# HydraBus_1_0_Rev1_2plus.net
KiCad netlist of a schematic drawn in EAGLE
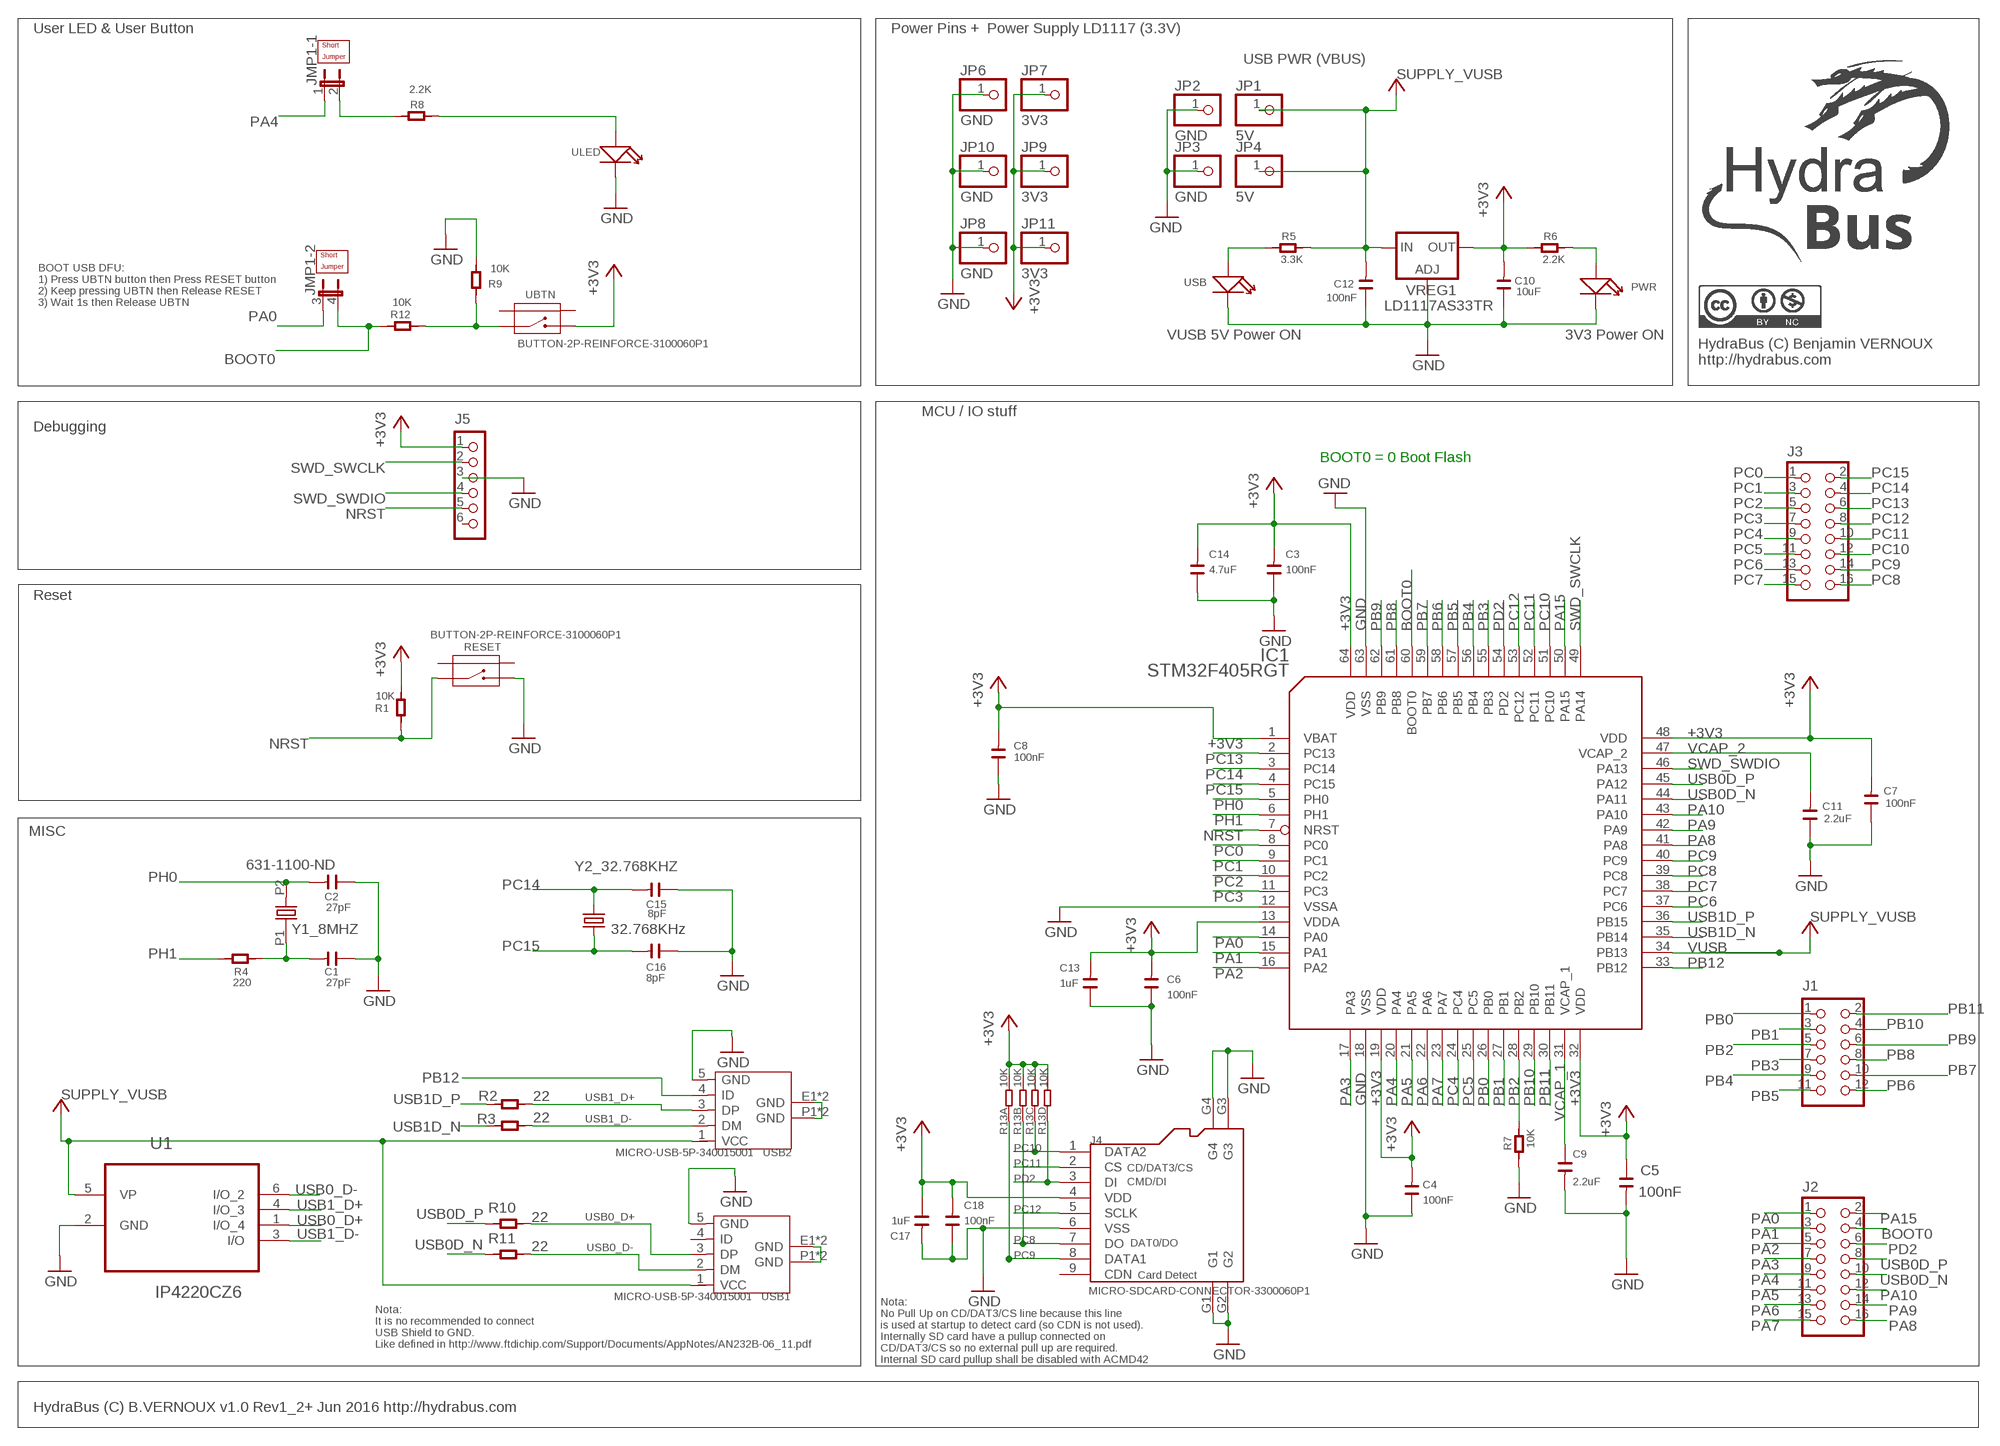
[diagram p0: schematic, sheet 1]

(export (version "E")
  (design (tool "Eeschema 10.0.6"))
  (components
    (comp (ref "C1")
      (value "27pF")
      (footprint "eagle-import:C0603")
      (libsource (lib "eagle-import") (part "C-0603"))
    )
    (comp (ref "C2")
      (value "27pF")
      (footprint "eagle-import:C0603")
      (libsource (lib "eagle-import") (part "C-0603"))
    )
    (comp (ref "C3")
      (value "100nF")
      (footprint "eagle-import:C0603")
      (libsource (lib "eagle-import") (part "C-0603"))
    )
    (comp (ref "C4")
      (value "100nF")
      (footprint "eagle-import:C0603")
      (libsource (lib "eagle-import") (part "C-0603"))
    )
    (comp (ref "C5")
      (value "100nF")
      (footprint "eagle-import:C0603")
      (libsource (lib "eagle-import") (part "C-0603"))
    )
    (comp (ref "C6")
      (value "100nF")
      (footprint "eagle-import:C0603")
      (libsource (lib "eagle-import") (part "C-0603"))
    )
    (comp (ref "C7")
      (value "100nF")
      (footprint "eagle-import:C0603")
      (libsource (lib "eagle-import") (part "C-0603"))
    )
    (comp (ref "C8")
      (value "100nF")
      (footprint "eagle-import:C0603")
      (libsource (lib "eagle-import") (part "C-0603"))
    )
    (comp (ref "C9")
      (value "2.2uF")
      (footprint "eagle-import:C0603")
      (libsource (lib "eagle-import") (part "C-0603"))
    )
    (comp (ref "C10")
      (value "10uF")
      (footprint "eagle-import:C0805")
      (libsource (lib "eagle-import") (part "C-0805"))
    )
    (comp (ref "C11")
      (value "2.2uF")
      (footprint "eagle-import:C0603")
      (libsource (lib "eagle-import") (part "C-0603"))
    )
    (comp (ref "C12")
      (value "100nF")
      (footprint "eagle-import:C0603")
      (libsource (lib "eagle-import") (part "C-0603"))
    )
    (comp (ref "C13")
      (value "1uF")
      (footprint "eagle-import:C0603")
      (libsource (lib "eagle-import") (part "C-0603"))
    )
    (comp (ref "C14")
      (value "4.7uF")
      (footprint "eagle-import:C0603")
      (libsource (lib "eagle-import") (part "C-0603"))
    )
    (comp (ref "C15")
      (value "8pF")
      (footprint "eagle-import:C0603")
      (libsource (lib "eagle-import") (part "C-0603"))
    )
    (comp (ref "C16")
      (value "8pF")
      (footprint "eagle-import:C0603")
      (libsource (lib "eagle-import") (part "C-0603"))
    )
    (comp (ref "C17")
      (value "1uF")
      (footprint "eagle-import:C0603")
      (libsource (lib "eagle-import") (part "C-0603"))
    )
    (comp (ref "C18")
      (value "100nF")
      (footprint "eagle-import:C0603")
      (libsource (lib "eagle-import") (part "C-0603"))
    )
    (comp (ref "IC1")
      (value "STM32F405RGT")
      (footprint "eagle-import:LQFP64")
      (libsource (lib "eagle-import") (part "STM32F405RTG"))
    )
    (comp (ref "J1")
      (value "CON_HEADER_2X06")
      (footprint "eagle-import:M2X6")
      (libsource (lib "eagle-import") (part "CON_HEADER_2X06"))
    )
    (comp (ref "J2")
      (value "CON_HEADER_2X08")
      (footprint "eagle-import:M2X8")
      (libsource (lib "eagle-import") (part "CON_HEADER_2X08"))
    )
    (comp (ref "J3")
      (value "CON_HEADER_2X08")
      (footprint "eagle-import:M2X8")
      (libsource (lib "eagle-import") (part "CON_HEADER_2X08"))
    )
    (comp (ref "J4")
      (value "MICRO-SDCARD-CONNECTOR-3300060P1")
      (footprint "eagle-import:9P-SMD-W-RING")
      (libsource (lib "eagle-import") (part "MICRO-SDCARD-CONNECTOR-3300060P1"))
    )
    (comp (ref "J5")
      (value "CON_HEADER_1X06-PTH")
      (footprint "eagle-import:M1X6")
      (libsource (lib "eagle-import") (part "CON_HEADER_1X06-PTH"))
    )
    (comp (ref "JMP1")
      (value "JP2QE")
      (footprint "eagle-import:JP2Q")
      (libsource (lib "eagle-import") (part "JP2QE"))
    )
    (comp (ref "JMP_UBTN")
      (value "SHORT-JUMPER-2P-3460440P1")
      (footprint "eagle-import:2P-2.54")
      (libsource (lib "eagle-import") (part "SHORT-JUMPER-2P-3460440P1"))
    )
    (comp (ref "JMP_ULED")
      (value "SHORT-JUMPER-2P-3460440P1")
      (footprint "eagle-import:2P-2.54")
      (libsource (lib "eagle-import") (part "SHORT-JUMPER-2P-3460440P1"))
    )
    (comp (ref "JP1")
      (value "5V")
      (footprint "eagle-import:1X01")
      (libsource (lib "eagle-import") (part "PINHD-1X1"))
    )
    (comp (ref "JP2")
      (value "GND")
      (footprint "eagle-import:1X01")
      (libsource (lib "eagle-import") (part "PINHD-1X1"))
    )
    (comp (ref "JP3")
      (value "GND")
      (footprint "eagle-import:1X01")
      (libsource (lib "eagle-import") (part "PINHD-1X1"))
    )
    (comp (ref "JP4")
      (value "5V")
      (footprint "eagle-import:1X01")
      (libsource (lib "eagle-import") (part "PINHD-1X1"))
    )
    (comp (ref "JP6")
      (value "GND")
      (footprint "eagle-import:1X01")
      (libsource (lib "eagle-import") (part "PINHD-1X1"))
    )
    (comp (ref "JP7")
      (value "3V3")
      (footprint "eagle-import:1X01")
      (libsource (lib "eagle-import") (part "PINHD-1X1"))
    )
    (comp (ref "JP8")
      (value "GND")
      (footprint "eagle-import:1X01")
      (libsource (lib "eagle-import") (part "PINHD-1X1"))
    )
    (comp (ref "JP9")
      (value "3V3")
      (footprint "eagle-import:1X01")
      (libsource (lib "eagle-import") (part "PINHD-1X1"))
    )
    (comp (ref "JP10")
      (value "GND")
      (footprint "eagle-import:1X01")
      (libsource (lib "eagle-import") (part "PINHD-1X1"))
    )
    (comp (ref "JP11")
      (value "3V3")
      (footprint "eagle-import:1X01")
      (libsource (lib "eagle-import") (part "PINHD-1X1"))
    )
    (comp (ref "PWR")
      (value "LED")
      (footprint "eagle-import:LED0603")
      (libsource (lib "eagle-import") (part "LED"))
    )
    (comp (ref "R1")
      (value "10K")
      (footprint "eagle-import:R0603")
      (libsource (lib "eagle-import") (part "R-0603"))
    )
    (comp (ref "R2")
      (value "22")
      (footprint "eagle-import:R0603")
      (libsource (lib "eagle-import") (part "R-0603"))
    )
    (comp (ref "R3")
      (value "22")
      (footprint "eagle-import:R0603")
      (libsource (lib "eagle-import") (part "R-0603"))
    )
    (comp (ref "R4")
      (value "220")
      (footprint "eagle-import:R0603")
      (libsource (lib "eagle-import") (part "R-0603"))
    )
    (comp (ref "R5")
      (value "3.3K")
      (footprint "eagle-import:R0603")
      (libsource (lib "eagle-import") (part "R-0603"))
    )
    (comp (ref "R6")
      (value "2.2K")
      (footprint "eagle-import:R0603")
      (libsource (lib "eagle-import") (part "R-0603"))
    )
    (comp (ref "R7")
      (value "10K")
      (footprint "eagle-import:R0603")
      (libsource (lib "eagle-import") (part "R-0603"))
    )
    (comp (ref "R8")
      (value "2.2K")
      (footprint "eagle-import:R0603")
      (libsource (lib "eagle-import") (part "R-0603"))
    )
    (comp (ref "R9")
      (value "10K")
      (footprint "eagle-import:R0603")
      (libsource (lib "eagle-import") (part "R-0603"))
    )
    (comp (ref "R10")
      (value "22")
      (footprint "eagle-import:R0603")
      (libsource (lib "eagle-import") (part "R-0603"))
    )
    (comp (ref "R11")
      (value "22")
      (footprint "eagle-import:R0603")
      (libsource (lib "eagle-import") (part "R-0603"))
    )
    (comp (ref "R12")
      (value "10K")
      (footprint "eagle-import:R0603")
      (libsource (lib "eagle-import") (part "R-0603"))
    )
    (comp (ref "R13")
      (value "10K")
      (footprint "eagle-import:R1206-8")
      (fields (field (name "OPL") "0040070P1 SMD RES ARRAY 10K OHM 4 RES 1206"))
      (libsource (lib "eagle-import") (part "R-4R"))
    )
    (comp (ref "RESET")
      (value "BUTTON-2P-REINFORCE-3100060P1")
      (footprint "eagle-import:4P-SMD-7.0X3.5X3.5H-90D")
      (libsource (lib "eagle-import") (part "BUTTON-2P-REINFORCE-3100060P1"))
    )
    (comp (ref "U1")
      (value "IP4220CZ6")
      (footprint "eagle-import:SOT95P275X110-6N")
      (libsource (lib "eagle-import") (part "IP4220CZ6"))
    )
    (comp (ref "UBTN")
      (value "BUTTON-2P-REINFORCE-3100060P1")
      (footprint "eagle-import:4P-SMD-7.0X3.5X3.5H-90D")
      (libsource (lib "eagle-import") (part "BUTTON-2P-REINFORCE-3100060P1"))
    )
    (comp (ref "ULED")
      (value "LED")
      (footprint "eagle-import:LED0603")
      (libsource (lib "eagle-import") (part "LED"))
    )
    (comp (ref "USB")
      (value "LED")
      (footprint "eagle-import:LED0603")
      (libsource (lib "eagle-import") (part "LED"))
    )
    (comp (ref "USB1")
      (value "MICRO-USB-5P-340015001")
      (footprint "eagle-import:B-SMD-5P")
      (libsource (lib "eagle-import") (part "MICRO-USB-5P-340015001"))
    )
    (comp (ref "USB2")
      (value "MICRO-USB-5P-340015001")
      (footprint "eagle-import:B-SMD-5P")
      (libsource (lib "eagle-import") (part "MICRO-USB-5P-340015001"))
    )
    (comp (ref "VREG1")
      (value "LD1117AS33TR")
      (footprint "eagle-import:SOT223")
      (libsource (lib "eagle-import") (part "LD117A?S33TR"))
    )
    (comp (ref "Y1_8MHZ")
      (value "631-1100-ND")
      (footprint "eagle-import:HC-49U-PTH")
      (libsource (lib "eagle-import") (part "OSC-XTAL-HC-49U-PTH"))
    )
    (comp (ref "Y2_32.768KHZ")
      (value "32.768KHz")
      (footprint "eagle-import:TC38H")
      (libsource (lib "eagle-import") (part "CRYSTALTC38H"))
    )
  )
  (nets
    (net (code "1") (name "+3V3") (class "Default")
      (node (ref "C10") (pin "1") (pinfunction "1_1") (pintype "bidirectional"))
      (node (ref "C13") (pin "1") (pinfunction "1_1") (pintype "bidirectional"))
      (node (ref "C14") (pin "1") (pinfunction "1_1") (pintype "bidirectional"))
      (node (ref "C17") (pin "2") (pinfunction "2_2") (pintype "bidirectional"))
      (node (ref "C18") (pin "1") (pinfunction "1_1") (pintype "bidirectional"))
      (node (ref "C3") (pin "1") (pinfunction "1_1") (pintype "bidirectional"))
      (node (ref "C4") (pin "1") (pinfunction "1_1") (pintype "bidirectional"))
      (node (ref "C5") (pin "2") (pinfunction "2_2") (pintype "bidirectional"))
      (node (ref "C6") (pin "1") (pinfunction "1_1") (pintype "bidirectional"))
      (node (ref "C7") (pin "1") (pinfunction "1_1") (pintype "bidirectional"))
      (node (ref "C8") (pin "1") (pinfunction "1_1") (pintype "bidirectional"))
      (node (ref "IC1") (pin "1") (pinfunction "VBAT_1") (pintype "power_in"))
      (node (ref "IC1") (pin "13") (pinfunction "VDDA_13") (pintype "power_in"))
      (node (ref "IC1") (pin "19") (pinfunction "VDD_19") (pintype "power_in"))
      (node (ref "IC1") (pin "32") (pinfunction "VDD_32") (pintype "power_in"))
      (node (ref "IC1") (pin "48") (pinfunction "VDD_48") (pintype "power_in"))
      (node (ref "IC1") (pin "64") (pinfunction "VDD_64") (pintype "power_in"))
      (node (ref "J4") (pin "4") (pinfunction "VDD_4") (pintype "bidirectional"))
      (node (ref "J5") (pin "1") (pinfunction "1_1") (pintype "bidirectional"))
      (node (ref "JP11") (pin "1") (pinfunction "1_1") (pintype "passive"))
      (node (ref "JP7") (pin "1") (pinfunction "1_1") (pintype "passive"))
      (node (ref "JP9") (pin "1") (pinfunction "1_1") (pintype "passive"))
      (node (ref "R1") (pin "2") (pinfunction "2_2") (pintype "bidirectional"))
      (node (ref "R13") (pin "5") (pinfunction "2_5") (pintype "passive"))
      (node (ref "R13") (pin "6") (pinfunction "2_6") (pintype "passive"))
      (node (ref "R13") (pin "7") (pinfunction "2_7") (pintype "passive"))
      (node (ref "R13") (pin "8") (pinfunction "2_8") (pintype "passive"))
      (node (ref "R6") (pin "2") (pinfunction "2_2") (pintype "bidirectional"))
      (node (ref "UBTN") (pin "2") (pinfunction "2_2") (pintype "bidirectional"))
      (node (ref "VREG1") (pin "4") (pinfunction "OUT_4") (pintype "passive"))
    )
    (net (code "2") (name "/BOOT0") (class "Default")
      (node (ref "IC1") (pin "60") (pinfunction "BOOT0_60") (pintype "bidirectional"))
      (node (ref "J2") (pin "4") (pinfunction "4_4") (pintype "passive"))
      (node (ref "JMP1") (pin "4") (pinfunction "2_4") (pintype "passive"))
      (node (ref "R12") (pin "2") (pinfunction "2_2") (pintype "bidirectional"))
    )
    (net (code "3") (name "/NRST") (class "Default")
      (node (ref "IC1") (pin "7") (pinfunction "NRST_7") (pintype "input"))
      (node (ref "J5") (pin "5") (pinfunction "5_5") (pintype "passive"))
      (node (ref "R1") (pin "1") (pinfunction "1_1") (pintype "bidirectional"))
      (node (ref "RESET") (pin "1") (pinfunction "1_1") (pintype "bidirectional"))
    )
    (net (code "4") (name "/PA0") (class "Default")
      (node (ref "IC1") (pin "14") (pinfunction "PA0_14") (pintype "bidirectional"))
      (node (ref "J2") (pin "1") (pinfunction "1_1") (pintype "passive"))
      (node (ref "JMP1") (pin "3") (pinfunction "1_3") (pintype "passive"))
    )
    (net (code "5") (name "/PA1") (class "Default")
      (node (ref "IC1") (pin "15") (pinfunction "PA1_15") (pintype "bidirectional"))
      (node (ref "J2") (pin "3") (pinfunction "3_3") (pintype "passive"))
    )
    (net (code "6") (name "/PA2") (class "Default")
      (node (ref "IC1") (pin "16") (pinfunction "PA2_16") (pintype "bidirectional"))
      (node (ref "J2") (pin "5") (pinfunction "5_5") (pintype "passive"))
    )
    (net (code "7") (name "/PA3") (class "Default")
      (node (ref "IC1") (pin "17") (pinfunction "PA3_17") (pintype "bidirectional"))
      (node (ref "J2") (pin "7") (pinfunction "7_7") (pintype "passive"))
    )
    (net (code "8") (name "/PA4") (class "Default")
      (node (ref "IC1") (pin "20") (pinfunction "PA4_20") (pintype "bidirectional"))
      (node (ref "J2") (pin "9") (pinfunction "9_9") (pintype "passive"))
      (node (ref "JMP1") (pin "1") (pinfunction "1_1") (pintype "passive"))
    )
    (net (code "9") (name "/PA5") (class "Default")
      (node (ref "IC1") (pin "21") (pinfunction "PA5_21") (pintype "bidirectional"))
      (node (ref "J2") (pin "11") (pinfunction "11_11") (pintype "passive"))
    )
    (net (code "10") (name "/PA6") (class "Default")
      (node (ref "IC1") (pin "22") (pinfunction "PA6_22") (pintype "bidirectional"))
      (node (ref "J2") (pin "13") (pinfunction "13_13") (pintype "passive"))
    )
    (net (code "11") (name "/PA7") (class "Default")
      (node (ref "IC1") (pin "23") (pinfunction "PA7_23") (pintype "bidirectional"))
      (node (ref "J2") (pin "15") (pinfunction "15_15") (pintype "passive"))
    )
    (net (code "12") (name "/PA8") (class "Default")
      (node (ref "IC1") (pin "41") (pinfunction "PA8_41") (pintype "bidirectional"))
      (node (ref "J2") (pin "16") (pinfunction "16_16") (pintype "passive"))
    )
    (net (code "13") (name "/PA9") (class "Default")
      (node (ref "IC1") (pin "42") (pinfunction "PA9_42") (pintype "bidirectional"))
      (node (ref "J2") (pin "14") (pinfunction "14_14") (pintype "passive"))
    )
    (net (code "14") (name "/PA10") (class "Default")
      (node (ref "IC1") (pin "43") (pinfunction "PA10_43") (pintype "bidirectional"))
      (node (ref "J2") (pin "12") (pinfunction "12_12") (pintype "passive"))
    )
    (net (code "15") (name "/PA15") (class "Default")
      (node (ref "IC1") (pin "50") (pinfunction "PA15_50") (pintype "bidirectional"))
      (node (ref "J2") (pin "2") (pinfunction "2_2") (pintype "passive"))
    )
    (net (code "16") (name "/PB0") (class "Default")
      (node (ref "IC1") (pin "26") (pinfunction "PB0_26") (pintype "bidirectional"))
      (node (ref "J1") (pin "1") (pinfunction "1_1") (pintype "passive"))
    )
    (net (code "17") (name "/PB1") (class "Default")
      (node (ref "IC1") (pin "27") (pinfunction "PB1_27") (pintype "bidirectional"))
      (node (ref "J1") (pin "3") (pinfunction "3_3") (pintype "passive"))
    )
    (net (code "18") (name "/PB2") (class "Default")
      (node (ref "IC1") (pin "28") (pinfunction "PB2_28") (pintype "bidirectional"))
      (node (ref "J1") (pin "5") (pinfunction "5_5") (pintype "passive"))
      (node (ref "R7") (pin "1") (pinfunction "1_1") (pintype "bidirectional"))
    )
    (net (code "19") (name "/PB3") (class "Default")
      (node (ref "IC1") (pin "55") (pinfunction "PB3_55") (pintype "bidirectional"))
      (node (ref "J1") (pin "7") (pinfunction "7_7") (pintype "passive"))
    )
    (net (code "20") (name "/PB4") (class "Default")
      (node (ref "IC1") (pin "56") (pinfunction "PB4_56") (pintype "bidirectional"))
      (node (ref "J1") (pin "9") (pinfunction "9_9") (pintype "passive"))
    )
    (net (code "21") (name "/PB5") (class "Default")
      (node (ref "IC1") (pin "57") (pinfunction "PB5_57") (pintype "bidirectional"))
      (node (ref "J1") (pin "11") (pinfunction "11_11") (pintype "passive"))
    )
    (net (code "22") (name "/PB6") (class "Default")
      (node (ref "IC1") (pin "58") (pinfunction "PB6_58") (pintype "bidirectional"))
      (node (ref "J1") (pin "12") (pinfunction "12_12") (pintype "passive"))
    )
    (net (code "23") (name "/PB7") (class "Default")
      (node (ref "IC1") (pin "59") (pinfunction "PB7_59") (pintype "bidirectional"))
      (node (ref "J1") (pin "10") (pinfunction "10_10") (pintype "passive"))
    )
    (net (code "24") (name "/PB8") (class "Default")
      (node (ref "IC1") (pin "61") (pinfunction "PB8_61") (pintype "bidirectional"))
      (node (ref "J1") (pin "8") (pinfunction "8_8") (pintype "passive"))
    )
    (net (code "25") (name "/PB9") (class "Default")
      (node (ref "IC1") (pin "62") (pinfunction "PB9_62") (pintype "bidirectional"))
      (node (ref "J1") (pin "6") (pinfunction "6_6") (pintype "passive"))
    )
    (net (code "26") (name "/PB10") (class "Default")
      (node (ref "IC1") (pin "29") (pinfunction "PB10_29") (pintype "bidirectional"))
      (node (ref "J1") (pin "4") (pinfunction "4_4") (pintype "passive"))
    )
    (net (code "27") (name "/PB11") (class "Default")
      (node (ref "IC1") (pin "30") (pinfunction "PB11_30") (pintype "bidirectional"))
      (node (ref "J1") (pin "2") (pinfunction "2_2") (pintype "passive"))
    )
    (net (code "28") (name "/PB12") (class "Default")
      (node (ref "IC1") (pin "33") (pinfunction "PB12_33") (pintype "bidirectional"))
      (node (ref "USB2") (pin "4") (pinfunction "ID_4") (pintype "bidirectional"))
    )
    (net (code "29") (name "/PC0") (class "Default")
      (node (ref "IC1") (pin "8") (pinfunction "PC0_8") (pintype "bidirectional"))
      (node (ref "J3") (pin "1") (pinfunction "1_1") (pintype "passive"))
    )
    (net (code "30") (name "/PC1") (class "Default")
      (node (ref "IC1") (pin "9") (pinfunction "PC1_9") (pintype "bidirectional"))
      (node (ref "J3") (pin "3") (pinfunction "3_3") (pintype "passive"))
    )
    (net (code "31") (name "/PC2") (class "Default")
      (node (ref "IC1") (pin "10") (pinfunction "PC2_10") (pintype "bidirectional"))
      (node (ref "J3") (pin "5") (pinfunction "5_5") (pintype "passive"))
    )
    (net (code "32") (name "/PC3") (class "Default")
      (node (ref "IC1") (pin "11") (pinfunction "PC3_11") (pintype "bidirectional"))
      (node (ref "J3") (pin "7") (pinfunction "7_7") (pintype "passive"))
    )
    (net (code "33") (name "/PC4") (class "Default")
      (node (ref "IC1") (pin "24") (pinfunction "PC4_24") (pintype "bidirectional"))
      (node (ref "J3") (pin "9") (pinfunction "9_9") (pintype "passive"))
    )
    (net (code "34") (name "/PC5") (class "Default")
      (node (ref "IC1") (pin "25") (pinfunction "PC5_25") (pintype "bidirectional"))
      (node (ref "J3") (pin "11") (pinfunction "11_11") (pintype "passive"))
    )
    (net (code "35") (name "/PC6") (class "Default")
      (node (ref "IC1") (pin "37") (pinfunction "PC6_37") (pintype "bidirectional"))
      (node (ref "J3") (pin "13") (pinfunction "13_13") (pintype "passive"))
    )
    (net (code "36") (name "/PC7") (class "Default")
      (node (ref "IC1") (pin "38") (pinfunction "PC7_38") (pintype "bidirectional"))
      (node (ref "J3") (pin "15") (pinfunction "15_15") (pintype "passive"))
    )
    (net (code "37") (name "/PC8") (class "Default")
      (node (ref "IC1") (pin "39") (pinfunction "PC8_39") (pintype "bidirectional"))
      (node (ref "J3") (pin "16") (pinfunction "16_16") (pintype "passive"))
      (node (ref "J4") (pin "7") (pinfunction "DO_7") (pintype "bidirectional"))
      (node (ref "R13") (pin "2") (pinfunction "1_2") (pintype "passive"))
    )
    (net (code "38") (name "/PC9") (class "Default")
      (node (ref "IC1") (pin "40") (pinfunction "PC9_40") (pintype "bidirectional"))
      (node (ref "J3") (pin "14") (pinfunction "14_14") (pintype "passive"))
      (node (ref "J4") (pin "8") (pinfunction "DATA1_8") (pintype "bidirectional"))
      (node (ref "R13") (pin "1") (pinfunction "1_1") (pintype "passive"))
    )
    (net (code "39") (name "/PC10") (class "Default")
      (node (ref "IC1") (pin "51") (pinfunction "PC10_51") (pintype "bidirectional"))
      (node (ref "J3") (pin "12") (pinfunction "12_12") (pintype "passive"))
      (node (ref "J4") (pin "1") (pinfunction "DATA2_1") (pintype "bidirectional"))
      (node (ref "R13") (pin "3") (pinfunction "1_3") (pintype "passive"))
    )
    (net (code "40") (name "/PC11") (class "Default")
      (node (ref "IC1") (pin "52") (pinfunction "PC11_52") (pintype "bidirectional"))
      (node (ref "J3") (pin "10") (pinfunction "10_10") (pintype "passive"))
      (node (ref "J4") (pin "2") (pinfunction "CS_2") (pintype "bidirectional"))
    )
    (net (code "41") (name "/PC12") (class "Default")
      (node (ref "IC1") (pin "53") (pinfunction "PC12_53") (pintype "bidirectional"))
      (node (ref "J3") (pin "8") (pinfunction "8_8") (pintype "passive"))
      (node (ref "J4") (pin "5") (pinfunction "SCLK_5") (pintype "bidirectional"))
    )
    (net (code "42") (name "/PC13") (class "Default")
      (node (ref "IC1") (pin "2") (pinfunction "PC13_2") (pintype "bidirectional"))
      (node (ref "J3") (pin "6") (pinfunction "6_6") (pintype "passive"))
    )
    (net (code "43") (name "/PC14") (class "Default")
      (node (ref "C15") (pin "1") (pinfunction "1_1") (pintype "bidirectional"))
      (node (ref "IC1") (pin "3") (pinfunction "PC14_3") (pintype "bidirectional"))
      (node (ref "J3") (pin "4") (pinfunction "4_4") (pintype "passive"))
      (node (ref "Y2_32.768KHZ") (pin "2") (pinfunction "2_2") (pintype "passive"))
    )
    (net (code "44") (name "/PC15") (class "Default")
      (node (ref "C16") (pin "1") (pinfunction "1_1") (pintype "bidirectional"))
      (node (ref "IC1") (pin "4") (pinfunction "PC15_4") (pintype "bidirectional"))
      (node (ref "J3") (pin "2") (pinfunction "2_2") (pintype "passive"))
      (node (ref "Y2_32.768KHZ") (pin "1") (pinfunction "1_1") (pintype "passive"))
    )
    (net (code "45") (name "/PD2") (class "Default")
      (node (ref "IC1") (pin "54") (pinfunction "PD2_54") (pintype "bidirectional"))
      (node (ref "J2") (pin "6") (pinfunction "6_6") (pintype "passive"))
      (node (ref "J4") (pin "3") (pinfunction "DI_3") (pintype "bidirectional"))
      (node (ref "R13") (pin "4") (pinfunction "1_4") (pintype "passive"))
    )
    (net (code "46") (name "/PH0") (class "Default")
      (node (ref "C2") (pin "1") (pinfunction "1_1") (pintype "bidirectional"))
      (node (ref "IC1") (pin "5") (pinfunction "PH0_5") (pintype "bidirectional"))
      (node (ref "Y1_8MHZ") (pin "P2") (pinfunction "2_P2") (pintype "passive"))
    )
    (net (code "47") (name "/PH1") (class "Default")
      (node (ref "IC1") (pin "6") (pinfunction "PH1_6") (pintype "bidirectional"))
      (node (ref "R4") (pin "2") (pinfunction "2_2") (pintype "bidirectional"))
    )
    (net (code "48") (name "/SWD_SWCLK") (class "Default")
      (node (ref "IC1") (pin "49") (pinfunction "PA14_49") (pintype "bidirectional"))
      (node (ref "J5") (pin "2") (pinfunction "2_2") (pintype "bidirectional"))
    )
    (net (code "49") (name "/SWD_SWDIO") (class "Default")
      (node (ref "IC1") (pin "46") (pinfunction "PA13_46") (pintype "bidirectional"))
      (node (ref "J5") (pin "4") (pinfunction "4_4") (pintype "passive"))
    )
    (net (code "50") (name "/USB0D_N") (class "Default")
      (node (ref "IC1") (pin "44") (pinfunction "PA11_44") (pintype "bidirectional"))
      (node (ref "J2") (pin "10") (pinfunction "10_10") (pintype "passive"))
      (node (ref "R11") (pin "2") (pinfunction "2_2") (pintype "bidirectional"))
    )
    (net (code "51") (name "/USB0D_P") (class "Default")
      (node (ref "IC1") (pin "45") (pinfunction "PA12_45") (pintype "bidirectional"))
      (node (ref "J2") (pin "8") (pinfunction "8_8") (pintype "passive"))
      (node (ref "R10") (pin "2") (pinfunction "2_2") (pintype "bidirectional"))
    )
    (net (code "52") (name "/USB0_D+") (class "Default")
      (node (ref "R10") (pin "1") (pinfunction "1_1") (pintype "bidirectional"))
      (node (ref "U1") (pin "1") (pinfunction "I/O_4_1") (pintype "bidirectional"))
      (node (ref "USB1") (pin "3") (pinfunction "DP_3") (pintype "bidirectional"))
    )
    (net (code "53") (name "/USB0_D-") (class "Default")
      (node (ref "R11") (pin "1") (pinfunction "1_1") (pintype "bidirectional"))
      (node (ref "U1") (pin "6") (pinfunction "I/O_2_6") (pintype "bidirectional"))
      (node (ref "USB1") (pin "2") (pinfunction "DM_2") (pintype "bidirectional"))
    )
    (net (code "54") (name "/USB1D_N") (class "Default")
      (node (ref "IC1") (pin "35") (pinfunction "PB14_35") (pintype "bidirectional"))
      (node (ref "R3") (pin "2") (pinfunction "2_2") (pintype "bidirectional"))
    )
    (net (code "55") (name "/USB1D_P") (class "Default")
      (node (ref "IC1") (pin "36") (pinfunction "PB15_36") (pintype "bidirectional"))
      (node (ref "R2") (pin "2") (pinfunction "2_2") (pintype "bidirectional"))
    )
    (net (code "56") (name "/USB1_D+") (class "Default")
      (node (ref "R2") (pin "1") (pinfunction "1_1") (pintype "bidirectional"))
      (node (ref "U1") (pin "4") (pinfunction "I/O_3_4") (pintype "bidirectional"))
      (node (ref "USB2") (pin "3") (pinfunction "DP_3") (pintype "bidirectional"))
    )
    (net (code "57") (name "/USB1_D-") (class "Default")
      (node (ref "R3") (pin "1") (pinfunction "1_1") (pintype "bidirectional"))
      (node (ref "U1") (pin "3") (pinfunction "I/O_3") (pintype "bidirectional"))
      (node (ref "USB2") (pin "2") (pinfunction "DM_2") (pintype "bidirectional"))
    )
    (net (code "58") (name "/VCAP_1") (class "Default")
      (node (ref "C9") (pin "2") (pinfunction "2_2") (pintype "bidirectional"))
      (node (ref "IC1") (pin "31") (pinfunction "VCAP_1_31") (pintype "passive"))
    )
    (net (code "59") (name "/VCAP_2") (class "Default")
      (node (ref "C11") (pin "1") (pinfunction "1_1") (pintype "bidirectional"))
      (node (ref "IC1") (pin "47") (pinfunction "VCAP_2_47") (pintype "passive"))
    )
    (net (code "60") (name "GND") (class "Default")
      (node (ref "C1") (pin "2") (pinfunction "2_2") (pintype "bidirectional"))
      (node (ref "C10") (pin "2") (pinfunction "2_2") (pintype "bidirectional"))
      (node (ref "C11") (pin "2") (pinfunction "2_2") (pintype "bidirectional"))
      (node (ref "C12") (pin "2") (pinfunction "2_2") (pintype "bidirectional"))
      (node (ref "C13") (pin "2") (pinfunction "2_2") (pintype "bidirectional"))
      (node (ref "C14") (pin "2") (pinfunction "2_2") (pintype "bidirectional"))
      (node (ref "C15") (pin "2") (pinfunction "2_2") (pintype "bidirectional"))
      (node (ref "C16") (pin "2") (pinfunction "2_2") (pintype "bidirectional"))
      (node (ref "C17") (pin "1") (pinfunction "1_1") (pintype "bidirectional"))
      (node (ref "C18") (pin "2") (pinfunction "2_2") (pintype "bidirectional"))
      (node (ref "C2") (pin "2") (pinfunction "2_2") (pintype "bidirectional"))
      (node (ref "C3") (pin "2") (pinfunction "2_2") (pintype "bidirectional"))
      (node (ref "C4") (pin "2") (pinfunction "2_2") (pintype "bidirectional"))
      (node (ref "C5") (pin "1") (pinfunction "1_1") (pintype "bidirectional"))
      (node (ref "C6") (pin "2") (pinfunction "2_2") (pintype "bidirectional"))
      (node (ref "C7") (pin "2") (pinfunction "2_2") (pintype "bidirectional"))
      (node (ref "C8") (pin "2") (pinfunction "2_2") (pintype "bidirectional"))
      (node (ref "C9") (pin "1") (pinfunction "1_1") (pintype "bidirectional"))
      (node (ref "IC1") (pin "12") (pinfunction "VSSA_12") (pintype "power_in"))
      (node (ref "IC1") (pin "18") (pinfunction "VSS_18") (pintype "power_in"))
      (node (ref "IC1") (pin "63") (pinfunction "VSS_63") (pintype "power_in"))
      (node (ref "J4") (pin "6") (pinfunction "VSS_6") (pintype "bidirectional"))
      (node (ref "J4") (pin "G1") (pinfunction "G1_G1") (pintype "bidirectional"))
      (node (ref "J4") (pin "G2") (pinfunction "G2_G2") (pintype "bidirectional"))
      (node (ref "J4") (pin "G3") (pinfunction "G3_G3") (pintype "bidirectional"))
      (node (ref "J4") (pin "G4") (pinfunction "G4_G4") (pintype "bidirectional"))
      (node (ref "J5") (pin "3") (pinfunction "3_3") (pintype "passive"))
      (node (ref "JP10") (pin "1") (pinfunction "1_1") (pintype "passive"))
      (node (ref "JP2") (pin "1") (pinfunction "1_1") (pintype "passive"))
      (node (ref "JP3") (pin "1") (pinfunction "1_1") (pintype "passive"))
      (node (ref "JP6") (pin "1") (pinfunction "1_1") (pintype "passive"))
      (node (ref "JP8") (pin "1") (pinfunction "1_1") (pintype "passive"))
      (node (ref "PWR") (pin "-") (pinfunction "-_-") (pintype "passive"))
      (node (ref "R7") (pin "2") (pinfunction "2_2") (pintype "bidirectional"))
      (node (ref "R9") (pin "2") (pinfunction "2_2") (pintype "bidirectional"))
      (node (ref "RESET") (pin "2") (pinfunction "2_2") (pintype "bidirectional"))
      (node (ref "U1") (pin "2") (pinfunction "GND_2") (pintype "passive"))
      (node (ref "ULED") (pin "-") (pinfunction "-_-") (pintype "passive"))
      (node (ref "USB") (pin "-") (pinfunction "-_-") (pintype "passive"))
      (node (ref "USB1") (pin "5") (pinfunction "GND_5") (pintype "bidirectional"))
      (node (ref "USB2") (pin "5") (pinfunction "GND_5") (pintype "bidirectional"))
      (node (ref "VREG1") (pin "1") (pinfunction "ADJ_1") (pintype "input"))
    )
    (net (code "61") (name "Net-(JMP1-Pad2)") (class "Default")
      (node (ref "JMP1") (pin "2") (pinfunction "2_2") (pintype "passive"))
      (node (ref "R8") (pin "2") (pinfunction "2_2") (pintype "bidirectional"))
    )
    (net (code "62") (name "Net-(PWR-Pad+)") (class "Default")
      (node (ref "PWR") (pin "+") (pinfunction "+_+") (pintype "passive"))
      (node (ref "R6") (pin "1") (pinfunction "1_1") (pintype "bidirectional"))
    )
    (net (code "63") (name "Net-(R5-Pad2)") (class "Default")
      (node (ref "R5") (pin "2") (pinfunction "2_2") (pintype "bidirectional"))
      (node (ref "USB") (pin "+") (pinfunction "+_+") (pintype "passive"))
    )
    (net (code "64") (name "Net-(R8-Pad1)") (class "Default")
      (node (ref "R8") (pin "1") (pinfunction "1_1") (pintype "bidirectional"))
      (node (ref "ULED") (pin "+") (pinfunction "+_+") (pintype "passive"))
    )
    (net (code "65") (name "Net-(R12-Pad1)") (class "Default")
      (node (ref "R12") (pin "1") (pinfunction "1_1") (pintype "bidirectional"))
      (node (ref "R9") (pin "1") (pinfunction "1_1") (pintype "bidirectional"))
      (node (ref "UBTN") (pin "1") (pinfunction "1_1") (pintype "bidirectional"))
    )
    (net (code "66") (name "Net-(USB1-GND-PadE1)") (class "Default")
      (node (ref "USB1") (pin "E1") (pinfunction "GND_E1") (pintype "bidirectional"))
      (node (ref "USB1") (pin "E2") (pinfunction "GND_E2") (pintype "bidirectional"))
      (node (ref "USB1") (pin "P1") (pinfunction "GND_P1") (pintype "bidirectional"))
      (node (ref "USB1") (pin "P2") (pinfunction "GND_P2") (pintype "bidirectional"))
    )
    (net (code "67") (name "Net-(USB2-GND-PadE1)") (class "Default")
      (node (ref "USB2") (pin "E1") (pinfunction "GND_E1") (pintype "bidirectional"))
      (node (ref "USB2") (pin "E2") (pinfunction "GND_E2") (pintype "bidirectional"))
      (node (ref "USB2") (pin "P1") (pinfunction "GND_P1") (pintype "bidirectional"))
      (node (ref "USB2") (pin "P2") (pinfunction "GND_P2") (pintype "bidirectional"))
    )
    (net (code "68") (name "Net-(Y1_8MHZ-1)") (class "Default")
      (node (ref "C1") (pin "1") (pinfunction "1_1") (pintype "bidirectional"))
      (node (ref "R4") (pin "1") (pinfunction "1_1") (pintype "bidirectional"))
      (node (ref "Y1_8MHZ") (pin "P1") (pinfunction "1_P1") (pintype "passive"))
    )
    (net (code "69") (name "SUPPLY_VUSB") (class "Default")
      (node (ref "C12") (pin "1") (pinfunction "1_1") (pintype "bidirectional"))
      (node (ref "IC1") (pin "34") (pinfunction "PB13_34") (pintype "bidirectional"))
      (node (ref "JP1") (pin "1") (pinfunction "1_1") (pintype "passive"))
      (node (ref "JP4") (pin "1") (pinfunction "1_1") (pintype "passive"))
      (node (ref "R5") (pin "1") (pinfunction "1_1") (pintype "bidirectional"))
      (node (ref "U1") (pin "5") (pinfunction "VP_5") (pintype "power_in"))
      (node (ref "USB1") (pin "1") (pinfunction "VCC_1") (pintype "bidirectional"))
      (node (ref "USB2") (pin "1") (pinfunction "VCC_1") (pintype "bidirectional"))
      (node (ref "VREG1") (pin "3") (pinfunction "IN_3") (pintype "input"))
    )
    (net (code "70") (name "unconnected-(J4-CDN-Pad9)") (class "Default")
      (node (ref "J4") (pin "9") (pinfunction "CDN_9") (pintype "bidirectional"))
    )
    (net (code "71") (name "unconnected-(J5-Pad6)") (class "Default")
      (node (ref "J5") (pin "6") (pinfunction "6_6") (pintype "passive"))
    )
    (net (code "72") (name "unconnected-(RESET-PadS1)") (class "Default")
      (node (ref "RESET") (pin "S1") (pinfunction "S1_S1") (pintype "bidirectional"))
    )
    (net (code "73") (name "unconnected-(RESET-PadS2)") (class "Default")
      (node (ref "RESET") (pin "S2") (pinfunction "S2_S2") (pintype "bidirectional"))
    )
    (net (code "74") (name "unconnected-(UBTN-PadS1)") (class "Default")
      (node (ref "UBTN") (pin "S1") (pinfunction "S1_S1") (pintype "bidirectional"))
    )
    (net (code "75") (name "unconnected-(UBTN-PadS2)") (class "Default")
      (node (ref "UBTN") (pin "S2") (pinfunction "S2_S2") (pintype "bidirectional"))
    )
    (net (code "76") (name "unconnected-(USB1-ID-Pad4)") (class "Default")
      (node (ref "USB1") (pin "4") (pinfunction "ID_4") (pintype "bidirectional"))
    )
  )
)
